# motor_pcb.net
KiCad netlist of a schematic drawn in EAGLE
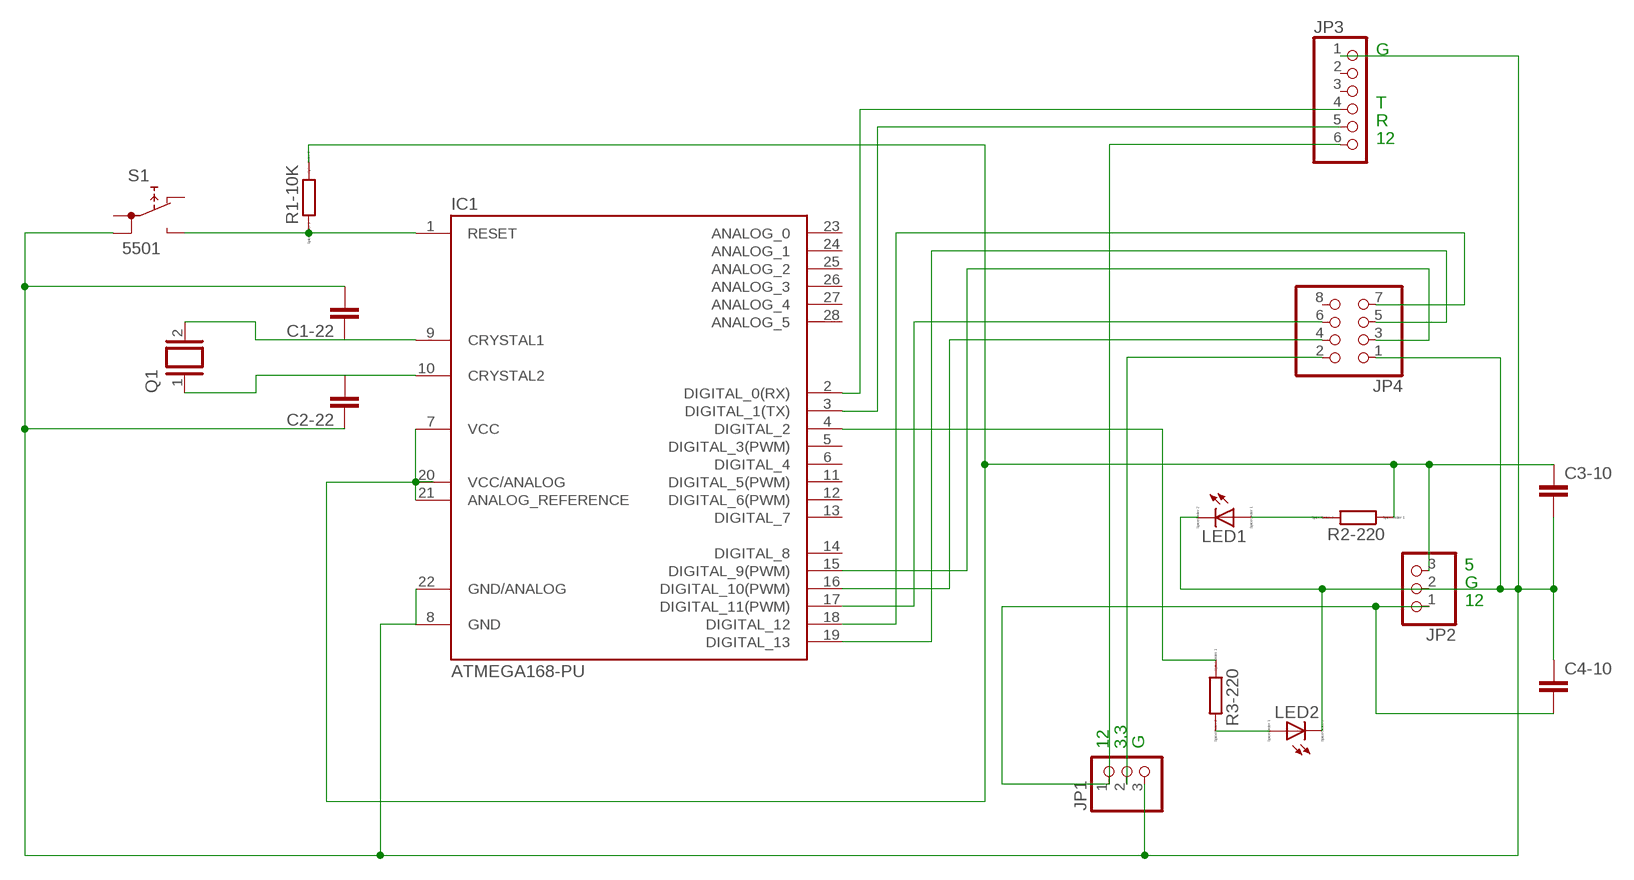
[diagram p0: schematic, sheet 1]

(export (version "E")
  (design (tool "Eeschema 10.0.6"))
  (components
    (comp (ref "C1-22")
      (value "C2.5/2")
      (footprint "eagle-import:C2.5-2")
      (libsource (lib "eagle-import") (part "C2.5/2"))
    )
    (comp (ref "C2-22")
      (value "C2.5/2")
      (footprint "eagle-import:C2.5-2")
      (libsource (lib "eagle-import") (part "C2.5/2"))
    )
    (comp (ref "C3-10")
      (value "C2.5/2")
      (footprint "eagle-import:C2.5-2")
      (libsource (lib "eagle-import") (part "C2.5/2"))
    )
    (comp (ref "C4-10")
      (value "C2.5/2")
      (footprint "eagle-import:C2.5-2")
      (libsource (lib "eagle-import") (part "C2.5/2"))
    )
    (comp (ref "IC1")
      (value "ATMEGA168-PU")
      (footprint "eagle-import:DIL28-3")
      (libsource (lib "eagle-import") (part "ATMEGA168-PU"))
    )
    (comp (ref "JP1")
      (value "PINHD-1X3")
      (footprint "eagle-import:1X03")
      (libsource (lib "eagle-import") (part "PINHD-1X3"))
    )
    (comp (ref "JP2")
      (value "PINHD-1X3")
      (footprint "eagle-import:1X03")
      (libsource (lib "eagle-import") (part "PINHD-1X3"))
    )
    (comp (ref "JP3")
      (value "PINHD-1X6")
      (footprint "eagle-import:1X06")
      (libsource (lib "eagle-import") (part "PINHD-1X6"))
    )
    (comp (ref "JP4")
      (value "PINHD-2X4")
      (footprint "eagle-import:2X04")
      (libsource (lib "eagle-import") (part "PINHD-2X4"))
    )
    (comp (ref "LED1")
      (value "LED_ELD260")
      (footprint "eagle-import:LED_LD260")
      (libsource (lib "eagle-import") (part "LED_ELD260"))
    )
    (comp (ref "LED2")
      (value "LED_ELD260")
      (footprint "eagle-import:LED_LD260")
      (libsource (lib "eagle-import") (part "LED_ELD260"))
    )
    (comp (ref "Q1")
      (value "XTAL/S")
      (footprint "eagle-import:QS")
      (libsource (lib "eagle-import") (part "XTAL/S"))
    )
    (comp (ref "R1-10K")
      (value "R0204/7")
      (footprint "eagle-import:0204_7")
      (libsource (lib "eagle-import") (part "R0204/7"))
    )
    (comp (ref "R2-220")
      (value "R0204/7")
      (footprint "eagle-import:0204_7")
      (libsource (lib "eagle-import") (part "R0204/7"))
    )
    (comp (ref "R3-220")
      (value "R0204/7")
      (footprint "eagle-import:0204_7")
      (libsource (lib "eagle-import") (part "R0204/7"))
    )
    (comp (ref "S1")
      (value "5501")
      (footprint "eagle-import:5501")
      (libsource (lib "eagle-import") (part "55?01"))
    )
  )
  (nets
    (net (code "1") (name "Net-(C4-10-Pad2)") (class "Default")
      (node (ref "C4-10") (pin "2") (pinfunction "2_2") (pintype "passive"))
      (node (ref "JP1") (pin "1") (pinfunction "1_1") (pintype "passive"))
      (node (ref "JP2") (pin "1") (pinfunction "1_1") (pintype "passive"))
      (node (ref "JP3") (pin "6") (pinfunction "6_6") (pintype "passive"))
    )
    (net (code "2") (name "Net-(IC1-ANALOG_REFERENCE)") (class "Default")
      (node (ref "C3-10") (pin "1") (pinfunction "1_1") (pintype "passive"))
      (node (ref "IC1") (pin "20") (pinfunction "VCC/ANALOG_20") (pintype "passive"))
      (node (ref "IC1") (pin "21") (pinfunction "ANALOG_REFERENCE_21") (pintype "passive"))
      (node (ref "IC1") (pin "7") (pinfunction "VCC_7") (pintype "power_in"))
      (node (ref "JP2") (pin "3") (pinfunction "3_3") (pintype "passive"))
      (node (ref "R1-10K") (pin "2") (pinfunction "2_2") (pintype "passive"))
      (node (ref "R2-220") (pin "1") (pinfunction "1_1") (pintype "passive"))
    )
    (net (code "3") (name "Net-(IC1-CRYSTAL1)") (class "Default")
      (node (ref "C1-22") (pin "1") (pinfunction "1_1") (pintype "passive"))
      (node (ref "IC1") (pin "9") (pinfunction "CRYSTAL1_9") (pintype "bidirectional"))
      (node (ref "Q1") (pin "2") (pinfunction "2_2") (pintype "passive"))
    )
    (net (code "4") (name "Net-(IC1-CRYSTAL2)") (class "Default")
      (node (ref "C2-22") (pin "2") (pinfunction "2_2") (pintype "passive"))
      (node (ref "IC1") (pin "10") (pinfunction "CRYSTAL2_10") (pintype "bidirectional"))
      (node (ref "Q1") (pin "1") (pinfunction "1_1") (pintype "passive"))
    )
    (net (code "5") (name "Net-(IC1-DIGITAL_0(RX))") (class "Default")
      (node (ref "IC1") (pin "2") (pinfunction "DIGITAL_0(RX)_2") (pintype "bidirectional"))
      (node (ref "JP3") (pin "4") (pinfunction "4_4") (pintype "passive"))
    )
    (net (code "6") (name "Net-(IC1-DIGITAL_1(TX))") (class "Default")
      (node (ref "IC1") (pin "3") (pinfunction "DIGITAL_1(TX)_3") (pintype "bidirectional"))
      (node (ref "JP3") (pin "5") (pinfunction "5_5") (pintype "passive"))
    )
    (net (code "7") (name "Net-(IC1-DIGITAL_2)") (class "Default")
      (node (ref "IC1") (pin "4") (pinfunction "DIGITAL_2_4") (pintype "bidirectional"))
      (node (ref "R3-220") (pin "1") (pinfunction "1_1") (pintype "passive"))
    )
    (net (code "8") (name "Net-(IC1-DIGITAL_9(PWM))") (class "Default")
      (node (ref "IC1") (pin "15") (pinfunction "DIGITAL_9(PWM)_15") (pintype "bidirectional"))
      (node (ref "JP4") (pin "3") (pinfunction "3_3") (pintype "passive"))
    )
    (net (code "9") (name "Net-(IC1-DIGITAL_10(PWM))") (class "Default")
      (node (ref "IC1") (pin "16") (pinfunction "DIGITAL_10(PWM)_16") (pintype "bidirectional"))
      (node (ref "JP4") (pin "4") (pinfunction "4_4") (pintype "passive"))
    )
    (net (code "10") (name "Net-(IC1-DIGITAL_11(PWM))") (class "Default")
      (node (ref "IC1") (pin "17") (pinfunction "DIGITAL_11(PWM)_17") (pintype "bidirectional"))
      (node (ref "JP4") (pin "6") (pinfunction "6_6") (pintype "passive"))
    )
    (net (code "11") (name "Net-(IC1-DIGITAL_12)") (class "Default")
      (node (ref "IC1") (pin "18") (pinfunction "DIGITAL_12_18") (pintype "bidirectional"))
      (node (ref "JP4") (pin "7") (pinfunction "7_7") (pintype "passive"))
    )
    (net (code "12") (name "Net-(IC1-DIGITAL_13)") (class "Default")
      (node (ref "IC1") (pin "19") (pinfunction "DIGITAL_13_19") (pintype "bidirectional"))
      (node (ref "JP4") (pin "5") (pinfunction "5_5") (pintype "passive"))
    )
    (net (code "13") (name "Net-(IC1-GND)") (class "Default")
      (node (ref "C1-22") (pin "2") (pinfunction "2_2") (pintype "passive"))
      (node (ref "C2-22") (pin "1") (pinfunction "1_1") (pintype "passive"))
      (node (ref "C3-10") (pin "2") (pinfunction "2_2") (pintype "passive"))
      (node (ref "C4-10") (pin "1") (pinfunction "1_1") (pintype "passive"))
      (node (ref "IC1") (pin "22") (pinfunction "GND/ANALOG_22") (pintype "power_in"))
      (node (ref "IC1") (pin "8") (pinfunction "GND_8") (pintype "power_in"))
      (node (ref "JP1") (pin "3") (pinfunction "3_3") (pintype "passive"))
      (node (ref "JP2") (pin "2") (pinfunction "2_2") (pintype "passive"))
      (node (ref "JP3") (pin "1") (pinfunction "1_1") (pintype "passive"))
      (node (ref "JP4") (pin "1") (pinfunction "1_1") (pintype "passive"))
      (node (ref "LED1") (pin "K") (pinfunction "C_K") (pintype "passive"))
      (node (ref "LED2") (pin "K") (pinfunction "C_K") (pintype "passive"))
      (node (ref "S1") (pin "1B") (pinfunction "1B_1B") (pintype "passive"))
    )
    (net (code "14") (name "Net-(IC1-RESET)") (class "Default")
      (node (ref "IC1") (pin "1") (pinfunction "RESET_1") (pintype "bidirectional"))
      (node (ref "R1-10K") (pin "1") (pinfunction "1_1") (pintype "passive"))
      (node (ref "S1") (pin "NO") (pinfunction "NO_NO") (pintype "passive"))
    )
    (net (code "15") (name "Net-(JP1-Pad2)") (class "Default")
      (node (ref "JP1") (pin "2") (pinfunction "2_2") (pintype "passive"))
      (node (ref "JP4") (pin "2") (pinfunction "2_2") (pintype "passive"))
    )
    (net (code "16") (name "Net-(LED1-PadA)") (class "Default")
      (node (ref "LED1") (pin "A") (pinfunction "A_A") (pintype "passive"))
      (node (ref "R2-220") (pin "2") (pinfunction "2_2") (pintype "passive"))
    )
    (net (code "17") (name "Net-(LED2-PadA)") (class "Default")
      (node (ref "LED2") (pin "A") (pinfunction "A_A") (pintype "passive"))
      (node (ref "R3-220") (pin "2") (pinfunction "2_2") (pintype "passive"))
    )
    (net (code "18") (name "unconnected-(IC1-ANALOG_0-Pad23)") (class "Default")
      (node (ref "IC1") (pin "23") (pinfunction "ANALOG_0_23") (pintype "bidirectional"))
    )
    (net (code "19") (name "unconnected-(IC1-ANALOG_1-Pad24)") (class "Default")
      (node (ref "IC1") (pin "24") (pinfunction "ANALOG_1_24") (pintype "bidirectional"))
    )
    (net (code "20") (name "unconnected-(IC1-ANALOG_2-Pad25)") (class "Default")
      (node (ref "IC1") (pin "25") (pinfunction "ANALOG_2_25") (pintype "bidirectional"))
    )
    (net (code "21") (name "unconnected-(IC1-ANALOG_3-Pad26)") (class "Default")
      (node (ref "IC1") (pin "26") (pinfunction "ANALOG_3_26") (pintype "bidirectional"))
    )
    (net (code "22") (name "unconnected-(IC1-ANALOG_4-Pad27)") (class "Default")
      (node (ref "IC1") (pin "27") (pinfunction "ANALOG_4_27") (pintype "bidirectional"))
    )
    (net (code "23") (name "unconnected-(IC1-ANALOG_5-Pad28)") (class "Default")
      (node (ref "IC1") (pin "28") (pinfunction "ANALOG_5_28") (pintype "bidirectional"))
    )
    (net (code "24") (name "unconnected-(IC1-DIGITAL_3(PWM)-Pad5)") (class "Default")
      (node (ref "IC1") (pin "5") (pinfunction "DIGITAL_3(PWM)_5") (pintype "bidirectional"))
    )
    (net (code "25") (name "unconnected-(IC1-DIGITAL_4-Pad6)") (class "Default")
      (node (ref "IC1") (pin "6") (pinfunction "DIGITAL_4_6") (pintype "bidirectional"))
    )
    (net (code "26") (name "unconnected-(IC1-DIGITAL_5(PWM)-Pad11)") (class "Default")
      (node (ref "IC1") (pin "11") (pinfunction "DIGITAL_5(PWM)_11") (pintype "bidirectional"))
    )
    (net (code "27") (name "unconnected-(IC1-DIGITAL_6(PWM)-Pad12)") (class "Default")
      (node (ref "IC1") (pin "12") (pinfunction "DIGITAL_6(PWM)_12") (pintype "bidirectional"))
    )
    (net (code "28") (name "unconnected-(IC1-DIGITAL_7-Pad13)") (class "Default")
      (node (ref "IC1") (pin "13") (pinfunction "DIGITAL_7_13") (pintype "bidirectional"))
    )
    (net (code "29") (name "unconnected-(IC1-DIGITAL_8-Pad14)") (class "Default")
      (node (ref "IC1") (pin "14") (pinfunction "DIGITAL_8_14") (pintype "bidirectional"))
    )
    (net (code "30") (name "unconnected-(JP3-Pad2)") (class "Default")
      (node (ref "JP3") (pin "2") (pinfunction "2_2") (pintype "passive"))
    )
    (net (code "31") (name "unconnected-(JP3-Pad3)") (class "Default")
      (node (ref "JP3") (pin "3") (pinfunction "3_3") (pintype "passive"))
    )
    (net (code "32") (name "unconnected-(JP4-Pad8)") (class "Default")
      (node (ref "JP4") (pin "8") (pinfunction "8_8") (pintype "passive"))
    )
    (net (code "33") (name "unconnected-(S1-Pad1A)") (class "Default")
      (node (ref "S1") (pin "1A") (pinfunction "1A_1A") (pintype "passive"))
    )
    (net (code "34") (name "unconnected-(S1-PadNC)") (class "Default")
      (node (ref "S1") (pin "NC") (pinfunction "NC_NC") (pintype "passive"))
    )
  )
)
